# Sheet3.net
KiCad netlist of a schematic drawn in Altium Designer
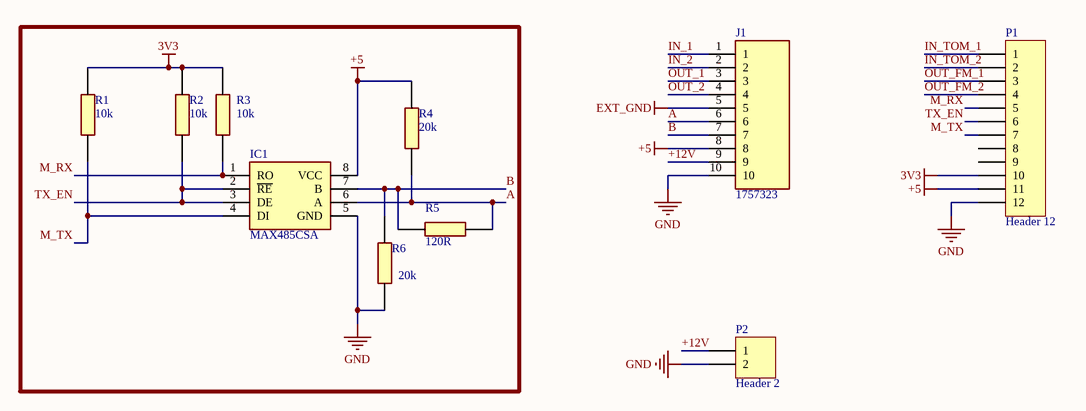
[diagram p0: Sheet3.SchDoc]

(export (version "E")
  (design (tool "Eeschema 10.0.6"))
  (components
    (comp (ref "IC1")
      (value "MAX485CSA")
      (footprint "BGA129C50P13X13_700X700X60:SOIC127P600X175-8N")
      (description "Integrated Circuit")
      (libsource (lib "*") (part "MAX485CSA"))
    )
    (comp (ref "J1")
      (value "1757323")
      (footprint "SamacSys:1757323")
      (description "Connector")
      (fields (field (name "MOUSER PART NUMBER") "651-1757323"))
      (libsource (lib "*") (part "1757323"))
    )
    (comp (ref "P1")
      (value "Header 12")
      (footprint "HDR1X12")
      (description "Header, 12-Pin")
      (fields (field (name "PUBLISHER") "Altium Limited"))
      (libsource (lib "Miscellaneous Connectors") (part "Header 12"))
    )
    (comp (ref "P2")
      (value "Header 2")
      (footprint "HDR1X2")
      (description "Header, 2-Pin")
      (fields (field (name "PUBLISHER") "Altium Limited"))
      (libsource (lib "Miscellaneous Connectors") (part "Header 2"))
    )
    (comp (ref "R1")
      (value "10k")
      (footprint "BGA129C50P13X13_700X700X60:RESC2012X60N")
      (description "Resistor")
      (fields
        (field (name "MANUFACTURER_PART_NUMBER") "CR0805-FX-1002ELF")
        (field (name "MOUSER PART NUMBER") "652-CR0805FX-1002ELF")
      )
      (libsource (lib "*") (part "CR0805-FX-1002ELF"))
    )
    (comp (ref "R2")
      (value "10k")
      (footprint "BGA129C50P13X13_700X700X60:RESC2012X60N")
      (description "Resistor")
      (fields
        (field (name "MANUFACTURER_PART_NUMBER") "CR0805-FX-1002ELF")
        (field (name "MOUSER PART NUMBER") "652-CR0805FX-1002ELF")
      )
      (libsource (lib "*") (part "CR0805-FX-1002ELF"))
    )
    (comp (ref "R3")
      (value "10k")
      (footprint "BGA129C50P13X13_700X700X60:RESC2012X60N")
      (description "Resistor")
      (fields
        (field (name "MANUFACTURER_PART_NUMBER") "CR0805-FX-1002ELF")
        (field (name "MOUSER PART NUMBER") "652-CR0805FX-1002ELF")
      )
      (libsource (lib "*") (part "CR0805-FX-1002ELF"))
    )
    (comp (ref "R4")
      (value "20k")
      (footprint "BGA129C50P13X13_700X700X60:RESC2012X60N")
      (description "Resistor")
      (fields
        (field (name "MANUFACTURER_PART_NUMBER") "CR0805-FX-2002ELF")
        (field (name "MOUSER PART NUMBER") "652-CR0805FX-2002ELF")
      )
      (libsource (lib "*") (part "CR0805-FX-2002ELF"))
    )
    (comp (ref "R5")
      (value "120R")
      (footprint "BGA129C50P13X13_700X700X60:RESC2012X60N")
      (description "Resistor")
      (fields
        (field (name "MANUFACTURER_PART_NUMBER") "CR0805-JW-121ELF")
        (field (name "MOUSER PART NUMBER") "652-CR0805JW-121ELF")
      )
      (libsource (lib "*") (part "CR0805-JW-121ELF"))
    )
    (comp (ref "R6")
      (value "20k")
      (footprint "BGA129C50P13X13_700X700X60:RESC2012X60N")
      (description "Resistor")
      (fields
        (field (name "MANUFACTURER_PART_NUMBER") "CR0805-FX-2002ELF")
        (field (name "MOUSER PART NUMBER") "652-CR0805FX-2002ELF")
      )
      (libsource (lib "*") (part "CR0805-FX-2002ELF"))
    )
  )
  (nets
    (net (code "1") (name "+5") (class "Default")
      (node (ref "IC1") (pin "8") (pinfunction "VCC_8") (pintype "passive"))
      (node (ref "J1") (pin "8") (pinfunction "8_8") (pintype "passive"))
      (node (ref "P1") (pin "11") (pinfunction "11_11") (pintype "passive"))
      (node (ref "R4") (pin "2") (pinfunction "2_2") (pintype "passive"))
    )
    (net (code "2") (name "/+12V") (class "Default")
      (node (ref "J1") (pin "9") (pinfunction "9_9") (pintype "passive"))
      (node (ref "P2") (pin "1") (pinfunction "1_1") (pintype "passive"))
    )
    (net (code "3") (name "/A") (class "Default")
      (node (ref "IC1") (pin "6") (pinfunction "A_6") (pintype "passive"))
      (node (ref "J1") (pin "6") (pinfunction "6_6") (pintype "passive"))
      (node (ref "R4") (pin "1") (pinfunction "1_1") (pintype "passive"))
      (node (ref "R5") (pin "2") (pinfunction "2_2") (pintype "passive"))
    )
    (net (code "4") (name "/B") (class "Default")
      (node (ref "IC1") (pin "7") (pinfunction "B_7") (pintype "passive"))
      (node (ref "J1") (pin "7") (pinfunction "7_7") (pintype "passive"))
      (node (ref "R5") (pin "1") (pinfunction "1_1") (pintype "passive"))
      (node (ref "R6") (pin "2") (pinfunction "2_2") (pintype "passive"))
    )
    (net (code "5") (name "/IN_1") (class "Default")
      (node (ref "J1") (pin "1") (pinfunction "1_1") (pintype "passive"))
    )
    (net (code "6") (name "/IN_2") (class "Default")
      (node (ref "J1") (pin "2") (pinfunction "2_2") (pintype "passive"))
    )
    (net (code "7") (name "/IN_TOM_1") (class "Default")
      (node (ref "P1") (pin "1") (pinfunction "1_1") (pintype "passive"))
    )
    (net (code "8") (name "/IN_TOM_2") (class "Default")
      (node (ref "P1") (pin "2") (pinfunction "2_2") (pintype "passive"))
    )
    (net (code "9") (name "/M_RX") (class "Default")
      (node (ref "IC1") (pin "1") (pinfunction "RO_1") (pintype "passive"))
      (node (ref "P1") (pin "5") (pinfunction "5_5") (pintype "passive"))
      (node (ref "R3") (pin "1") (pinfunction "1_1") (pintype "passive"))
    )
    (net (code "10") (name "/M_TX") (class "Default")
      (node (ref "IC1") (pin "4") (pinfunction "DI_4") (pintype "passive"))
      (node (ref "P1") (pin "7") (pinfunction "7_7") (pintype "passive"))
      (node (ref "R1") (pin "1") (pinfunction "1_1") (pintype "passive"))
    )
    (net (code "11") (name "/OUT_1") (class "Default")
      (node (ref "J1") (pin "3") (pinfunction "3_3") (pintype "passive"))
    )
    (net (code "12") (name "/OUT_2") (class "Default")
      (node (ref "J1") (pin "4") (pinfunction "4_4") (pintype "passive"))
    )
    (net (code "13") (name "/OUT_FM_1") (class "Default")
      (node (ref "P1") (pin "3") (pinfunction "3_3") (pintype "passive"))
    )
    (net (code "14") (name "/OUT_FM_2") (class "Default")
      (node (ref "P1") (pin "4") (pinfunction "4_4") (pintype "passive"))
    )
    (net (code "15") (name "/TX_EN") (class "Default")
      (node (ref "IC1") (pin "2") (pinfunction "~{RE}_2") (pintype "passive"))
      (node (ref "IC1") (pin "3") (pinfunction "DE_3") (pintype "passive"))
      (node (ref "P1") (pin "6") (pinfunction "6_6") (pintype "passive"))
      (node (ref "R2") (pin "1") (pinfunction "1_1") (pintype "passive"))
    )
    (net (code "16") (name "3V3") (class "Default")
      (node (ref "P1") (pin "10") (pinfunction "10_10") (pintype "passive"))
      (node (ref "R1") (pin "2") (pinfunction "2_2") (pintype "passive"))
      (node (ref "R2") (pin "2") (pinfunction "2_2") (pintype "passive"))
      (node (ref "R3") (pin "2") (pinfunction "2_2") (pintype "passive"))
    )
    (net (code "17") (name "EXT_GND") (class "Default")
      (node (ref "J1") (pin "5") (pinfunction "5_5") (pintype "passive"))
    )
    (net (code "18") (name "GND") (class "Default")
      (node (ref "IC1") (pin "5") (pinfunction "GND_5") (pintype "passive"))
      (node (ref "J1") (pin "10") (pinfunction "10_10") (pintype "passive"))
      (node (ref "P1") (pin "12") (pinfunction "12_12") (pintype "passive"))
      (node (ref "P2") (pin "2") (pinfunction "2_2") (pintype "passive"))
      (node (ref "R6") (pin "1") (pinfunction "1_1") (pintype "passive"))
    )
    (net (code "19") (name "unconnected-(P1-Pad8)") (class "Default")
      (node (ref "P1") (pin "8") (pinfunction "8_8") (pintype "passive"))
    )
    (net (code "20") (name "unconnected-(P1-Pad9)") (class "Default")
      (node (ref "P1") (pin "9") (pinfunction "9_9") (pintype "passive"))
    )
  )
)
